# Preamp.net
KiCad netlist of a schematic drawn in Altium Designer
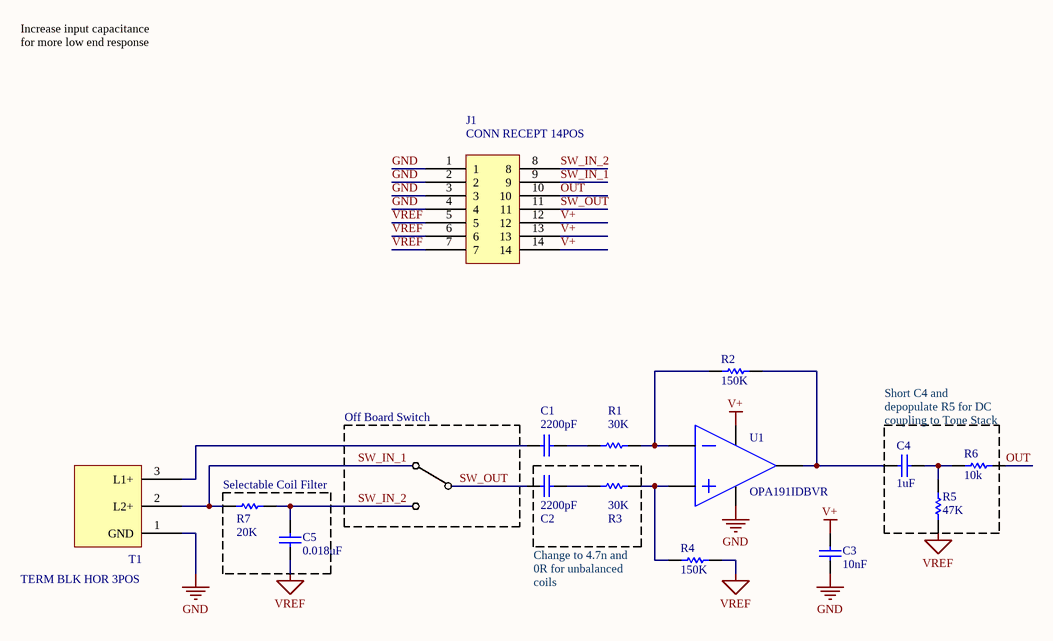
[diagram p0: Preamp.SchDoc]

(export (version "E")
  (design (tool "Eeschema 10.0.6"))
  (components
    (comp (ref "C1")
      (value "2200pF")
      (footprint "CAPC1608X09N")
      (description "2200pF ±1% 50V Ceramic Capacitor C0G, NP0 0603 (1608 Metric)")
      (fields (field (name "DIGIKEY PART NUMBER") "490-7768-1-ND") (field (name "MANUFACTURER") "Murata"))
      (libsource (lib "GuitarLibrary") (part "CAP CER 2200PF 50V C0G/NP0 0603"))
    )
    (comp (ref "C2")
      (value "2200pF")
      (footprint "CAPC1608X09N")
      (description "2200pF ±1% 50V Ceramic Capacitor C0G, NP0 0603 (1608 Metric)")
      (fields (field (name "DIGIKEY PART NUMBER") "490-7768-1-ND") (field (name "MANUFACTURER") "Murata"))
      (libsource (lib "GuitarLibrary") (part "CAP CER 2200PF 50V C0G/NP0 0603"))
    )
    (comp (ref "C3")
      (value "10nF")
      (footprint "CAPC1608X09N")
      (description "10000pF ±5% 50V Ceramic Capacitor C0G, NP0 0603 (1608 Metric)")
      (fields (field (name "DIGIKEY PART NUMBER") "490-9666-1-ND") (field (name "MANUFACTURER") "Murata"))
      (libsource (lib "GuitarLibrary") (part "CAP CER 10000PF 50V C0G/NP0 0603"))
    )
    (comp (ref "C4")
      (value "1uF")
      (footprint "CAPC1608X09N")
      (description "1µF ±10% 25V Ceramic Capacitor X7R 0603 (1608 Metric)")
      (fields (field (name "DIGIKEY PART NUMBER") "490-10673-1-ND") (field (name "VOLTAGE") "25V"))
      (libsource (lib "GuitarLibrary") (part "CAP CER 1UF 25V X7R 0603"))
    )
    (comp (ref "C5")
      (value "0.018uF")
      (footprint "CAPC1608X09N")
      (description "CAP CER 0.018UF 35V NP0 0603")
      (fields (field (name "DIGIKEY PART NUMBER") "445-174558-1-ND") (field (name "VOLTAGE") "35V"))
      (libsource (lib "GuitarLibrary") (part "CAP CER 0.018UF 35V NP0 0603"))
    )
    (comp (ref "J1")
      (value "CONN RECEPT 14POS")
      (footprint "DF12(3.0)-14DS")
      (description "14 Position Connector Receptacle, Center Strip Contacts Surface Mount Gold")
      (fields (field (name "MANUFACTURER") "Hirose") (field (name "DIGIKEY PART NUMBER") "H11702CT-ND"))
      (libsource (lib "GuitarLibrary") (part "DF12(3.0)-14DS-0.5V(86)"))
    )
    (comp (ref "R1")
      (value "30K")
      (footprint "RESC1608X06N")
      (description "RES SMD 30K OHM 1% 1/10W 0603")
      (fields (field (name "TOLERANCE") "1%") (field (name "DIGIKEY PART NUMBER") "311-30.0KHRCT-ND"))
      (libsource (lib "GuitarLibrary") (part "RES SMD 30K OHM 1% 1/10W 0603"))
    )
    (comp (ref "R2")
      (value "150K")
      (footprint "RESC1608X06N")
      (description "RES SMD 150K OHM 1% 1/10W 0603")
      (fields (field (name "TOLERANCE") "1%") (field (name "DIGIKEY PART NUMBER") "311-150KHRCT-ND"))
      (libsource (lib "GuitarLibrary") (part "RES SMD 150K OHM 1% 1/10W 0603"))
    )
    (comp (ref "R3")
      (value "30K")
      (footprint "RESC1608X06N")
      (description "RES SMD 30K OHM 1% 1/10W 0603")
      (fields (field (name "TOLERANCE") "1%") (field (name "DIGIKEY PART NUMBER") "311-30.0KHRCT-ND"))
      (libsource (lib "GuitarLibrary") (part "RES SMD 30K OHM 1% 1/10W 0603"))
    )
    (comp (ref "R4")
      (value "150K")
      (footprint "RESC1608X06N")
      (description "RES SMD 150K OHM 1% 1/10W 0603")
      (fields (field (name "TOLERANCE") "1%") (field (name "DIGIKEY PART NUMBER") "311-150KHRCT-ND"))
      (libsource (lib "GuitarLibrary") (part "RES SMD 150K OHM 1% 1/10W 0603"))
    )
    (comp (ref "R5")
      (value "47K")
      (footprint "RESC1608X06N")
      (description "RES 47K 0603")
      (fields (field (name "TOLERANCE") "1%") (field (name "DIGIKEY PART NUMBER") "311-47.0KHRCT-ND"))
      (libsource (lib "GuitarLibrary") (part "RES SMD 47K OHM 1% 1/10W 0603"))
    )
    (comp (ref "R6")
      (value "10k")
      (footprint "RESC1608X06N")
      (description "RES SMD 10K OHM 1% 1/10W 0603")
      (fields (field (name "TOLERANCE") "1%") (field (name "POWER") "0.1W"))
      (libsource (lib "GuitarLibrary") (part "RES SMD 10K OHM 1% 1/10W 0603"))
    )
    (comp (ref "R7")
      (value "20K")
      (footprint "RESC1608X06N")
      (description "RES SMD 20K OHM 1% 1/10W 0603")
      (fields (field (name "TOLERANCE") "1%") (field (name "DIGIKEY PART NUMBER") "311-20.0KHRCT-ND"))
      (libsource (lib "GuitarLibrary") (part "RES SMD 20K OHM 1% 1/10W 0603"))
    )
    (comp (ref "T1")
      (value "TERM BLK HOR 3POS")
      (footprint "TERM BLK HOR 3POS")
      (description "3 Position Wire to Board Terminal Block Horizontal with Board 0.100\" (2.54mm) Surface Mount")
      (fields (field (name "DIGIKEY PART NUMBER") "1195-3657-1-ND"))
      (libsource (lib "GuitarLibrary") (part "TERM BLK HOR 3POS"))
    )
    (comp (ref "U1")
      (value "OPA191IDBVR")
      (footprint "SOT23-5")
      (description "General Purpose Amplifier 1 Circuit Rail-to-Rail SOT-23-5")
      (fields (field (name "DIGIKEY PART NUMBER") "296-44386-1-ND"))
      (libsource (lib "GuitarLibrary") (part "OPA191IDBVR"))
    )
  )
  (nets
    (net (code "1") (name "/OUT") (class "Default")
      (node (ref "J1") (pin "10") (pinfunction "10_10") (pintype "passive"))
      (node (ref "R6") (pin "1") (pinfunction "1_1") (pintype "passive"))
    )
    (net (code "2") (name "/SW_IN_1") (class "Default")
      (node (ref "J1") (pin "9") (pinfunction "9_9") (pintype "passive"))
      (node (ref "R7") (pin "1") (pinfunction "1_1") (pintype "passive"))
      (node (ref "T1") (pin "2") (pinfunction "L2+_2") (pintype "passive"))
    )
    (net (code "3") (name "/SW_IN_2") (class "Default")
      (node (ref "C5") (pin "2") (pinfunction "2_2") (pintype "passive"))
      (node (ref "J1") (pin "8") (pinfunction "8_8") (pintype "passive"))
      (node (ref "R7") (pin "2") (pinfunction "2_2") (pintype "passive"))
    )
    (net (code "4") (name "/SW_OUT") (class "Default")
      (node (ref "C2") (pin "1") (pinfunction "1_1") (pintype "passive"))
      (node (ref "J1") (pin "11") (pinfunction "11_11") (pintype "passive"))
    )
    (net (code "5") (name "GND") (class "Default")
      (node (ref "C3") (pin "1") (pinfunction "1_1") (pintype "passive"))
      (node (ref "J1") (pin "1") (pinfunction "1_1") (pintype "passive"))
      (node (ref "J1") (pin "2") (pinfunction "2_2") (pintype "passive"))
      (node (ref "J1") (pin "3") (pinfunction "3_3") (pintype "passive"))
      (node (ref "J1") (pin "4") (pinfunction "4_4") (pintype "passive"))
      (node (ref "T1") (pin "1") (pinfunction "GND_1") (pintype "passive"))
      (node (ref "U1") (pin "2") (pinfunction "GND_2") (pintype "power_in"))
    )
    (net (code "6") (name "Net-(C1-Pad2)") (class "Default")
      (node (ref "C1") (pin "2") (pinfunction "2_2") (pintype "passive"))
      (node (ref "R1") (pin "1") (pinfunction "1_1") (pintype "passive"))
    )
    (net (code "7") (name "Net-(C2-Pad2)") (class "Default")
      (node (ref "C2") (pin "2") (pinfunction "2_2") (pintype "passive"))
      (node (ref "R3") (pin "1") (pinfunction "1_1") (pintype "passive"))
    )
    (net (code "8") (name "Net-(C4-Pad2)") (class "Default")
      (node (ref "C4") (pin "2") (pinfunction "2_2") (pintype "passive"))
      (node (ref "R5") (pin "2") (pinfunction "2_2") (pintype "passive"))
      (node (ref "R6") (pin "2") (pinfunction "2_2") (pintype "passive"))
    )
    (net (code "9") (name "Net-(T1-L1+)") (class "Default")
      (node (ref "C1") (pin "1") (pinfunction "1_1") (pintype "passive"))
      (node (ref "T1") (pin "3") (pinfunction "L1+_3") (pintype "passive"))
    )
    (net (code "10") (name "Net-(U1-VIN+)") (class "Default")
      (node (ref "R3") (pin "2") (pinfunction "2_2") (pintype "passive"))
      (node (ref "R4") (pin "1") (pinfunction "1_1") (pintype "passive"))
      (node (ref "U1") (pin "3") (pinfunction "VIN+_3") (pintype "passive"))
    )
    (net (code "11") (name "Net-(U1-VIN-)") (class "Default")
      (node (ref "R1") (pin "2") (pinfunction "2_2") (pintype "passive"))
      (node (ref "R2") (pin "1") (pinfunction "1_1") (pintype "passive"))
      (node (ref "U1") (pin "4") (pinfunction "VIN-_4") (pintype "passive"))
    )
    (net (code "12") (name "Net-(U1-VOUT)") (class "Default")
      (node (ref "C4") (pin "1") (pinfunction "1_1") (pintype "passive"))
      (node (ref "R2") (pin "2") (pinfunction "2_2") (pintype "passive"))
      (node (ref "U1") (pin "1") (pinfunction "VOUT_1") (pintype "passive"))
    )
    (net (code "13") (name "V+") (class "Default")
      (node (ref "C3") (pin "2") (pinfunction "2_2") (pintype "passive"))
      (node (ref "J1") (pin "12") (pinfunction "12_12") (pintype "passive"))
      (node (ref "J1") (pin "13") (pinfunction "13_13") (pintype "passive"))
      (node (ref "J1") (pin "14") (pinfunction "14_14") (pintype "passive"))
      (node (ref "U1") (pin "5") (pinfunction "V+_5") (pintype "power_in"))
    )
    (net (code "14") (name "VREF") (class "Default")
      (node (ref "C5") (pin "1") (pinfunction "1_1") (pintype "passive"))
      (node (ref "J1") (pin "5") (pinfunction "5_5") (pintype "passive"))
      (node (ref "J1") (pin "6") (pinfunction "6_6") (pintype "passive"))
      (node (ref "J1") (pin "7") (pinfunction "7_7") (pintype "passive"))
      (node (ref "R4") (pin "2") (pinfunction "2_2") (pintype "passive"))
      (node (ref "R5") (pin "1") (pinfunction "1_1") (pintype "passive"))
    )
  )
)
